# 485.net
KiCad netlist of a schematic drawn in Altium Designer
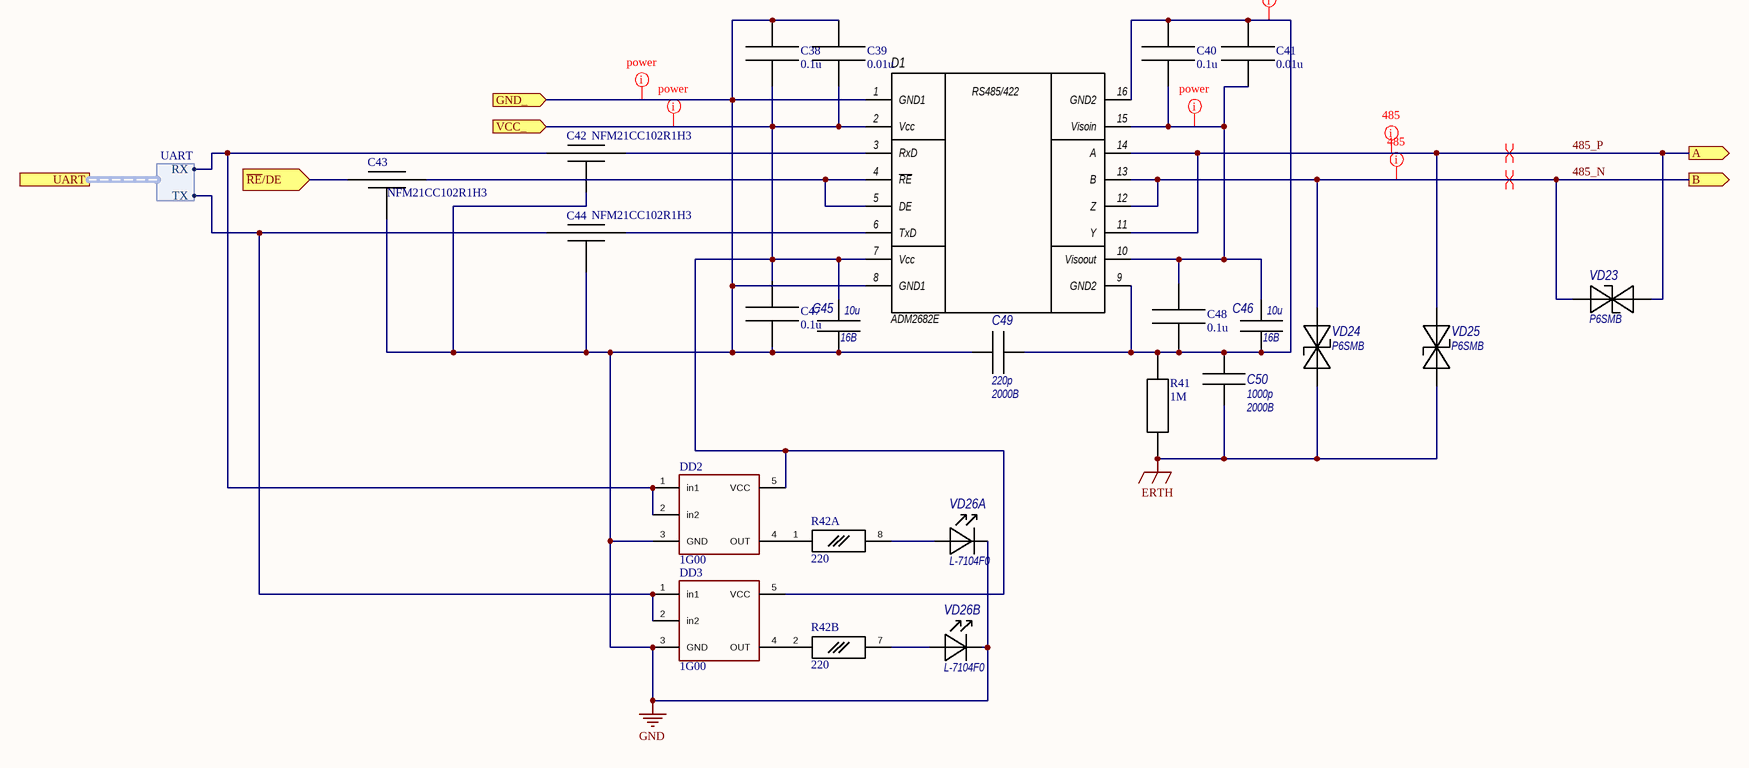
[diagram p0: 485.SchDoc]

(export (version "E")
  (design (tool "Eeschema 10.0.6"))
  (components
    (comp (ref "C38") (value "0.1u") (footprint "cap_0402") (libsource (lib "lib") (part "cap")))
    (comp (ref "C39") (value "0.01u") (footprint "cap_0402") (libsource (lib "lib") (part "cap")))
    (comp (ref "C40") (value "0.1u") (footprint "cap_0402") (libsource (lib "lib") (part "cap")))
    (comp (ref "C41") (value "0.01u") (footprint "cap_0402") (libsource (lib "lib") (part "cap")))
    (comp (ref "C42")
      (value "NFM21CC102R1H3")
      (footprint "NFM21C")
      (libsource (lib "altium-import") (part "root_0_NFM21C_"))
    )
    (comp (ref "C43")
      (value "NFM21CC102R1H3")
      (footprint "NFM21C")
      (libsource (lib "altium-import") (part "root_0_NFM21C_"))
    )
    (comp (ref "C44")
      (value "NFM21CC102R1H3")
      (footprint "NFM21C")
      (libsource (lib "altium-import") (part "root_0_NFM21C_"))
    )
    (comp (ref "C45")
      (value "10u")
      (footprint "C0805_")
      (fields (field (name "VOLTAGE") "16В") (field (name "Comment") "10u 16v"))
      (libsource (lib "altium-import") (part "root_1_Capacitor ceramic_"))
    )
    (comp (ref "C46")
      (value "10u")
      (footprint "C0805_")
      (fields (field (name "VOLTAGE") "16В") (field (name "Comment") "10u 16v"))
      (libsource (lib "altium-import") (part "root_1_Capacitor ceramic_"))
    )
    (comp (ref "C47") (value "0.1u") (footprint "cap_0402") (libsource (lib "lib") (part "cap")))
    (comp (ref "C48") (value "0.1u") (footprint "cap_0402") (libsource (lib "lib") (part "cap")))
    (comp (ref "C49")
      (value "220p")
      (footprint "C1206_")
      (fields (field (name "VOLTAGE") "2000В") (field (name "Comment") "220p 2000v"))
      (libsource (lib "altium-import") (part "root_0_Capacitor ceramic_"))
    )
    (comp (ref "C50")
      (value "1000p")
      (footprint "C1206_")
      (fields (field (name "VOLTAGE") "2000В") (field (name "Comment") "1000p 2000v"))
      (libsource (lib "altium-import") (part "root_1_Capacitor ceramic_"))
    )
    (comp (ref "D1")
      (value "ADM2682E_RS485_422_Isol")
      (footprint "SOIC_16IC_")
      (fields (field (name "TYPE") "ADM2682E"))
      (libsource (lib "altium-import") (part "root_0_ADM2682E_RS485_422_Isol_"))
    )
    (comp (ref "DD2")
      (value "1G00")
      (footprint "sot-23-5")
      (description "2NAND")
      (libsource (lib "lib") (part "1G00"))
    )
    (comp (ref "DD3")
      (value "1G00")
      (footprint "sot-23-5")
      (description "2NAND")
      (libsource (lib "lib") (part "1G00"))
    )
    (comp (ref "R41") (value "1M") (footprint "Lib:0805-res") (libsource (lib "lib") (part "res")))
    (comp (ref "R42")
      (value "220")
      (footprint "YC164")
      (description "YC164")
      (libsource (lib "my_sch_lib") (part "res_array"))
    )
    (comp (ref "VD23")
      (value "PTVS33VS1UTR")
      (footprint "SOD-123")
      (description "PTVS33VS1UTR,115, TVS DIODE 33VWM 53.3VC SOD123W")
      (fields (field (name "TYPE") "P6SMB"))
      (libsource (lib "lib") (part "PTVS33VS1UTR"))
    )
    (comp (ref "VD24")
      (value "PTVS33VS1UTR")
      (footprint "SOD-123")
      (description "PTVS33VS1UTR,115, TVS DIODE 33VWM 53.3VC SOD123W")
      (fields (field (name "TYPE") "P6SMB"))
      (libsource (lib "lib") (part "PTVS33VS1UTR"))
    )
    (comp (ref "VD25")
      (value "PTVS33VS1UTR")
      (footprint "SOD-123")
      (description "PTVS33VS1UTR,115, TVS DIODE 33VWM 53.3VC SOD123W")
      (fields (field (name "TYPE") "P6SMB"))
      (libsource (lib "lib") (part "PTVS33VS1UTR"))
    )
    (comp (ref "VD26")
      (value "Diod_sv_L-7104F0")
      (footprint "L-7104_")
      (fields (field (name "TYPE") "L-7104F0"))
      (libsource (lib "my_sch_lib") (part "Diod_sv_L-7104F0"))
    )
  )
  (nets
    (net (code "2") (name "/485_N") (class "Default")
      (node (ref "D1") (pin "12") (pinfunction "Z_12") (pintype "passive"))
      (node (ref "D1") (pin "13") (pinfunction "B_13") (pintype "passive"))
      (node (ref "VD23") (pin "K") (pinfunction "K_K") (pintype "passive"))
      (node (ref "VD24") (pin "K") (pinfunction "K_K") (pintype "passive"))
    )
    (net (code "3") (name "/485_P") (class "Default")
      (node (ref "D1") (pin "11") (pinfunction "Y_11") (pintype "passive"))
      (node (ref "D1") (pin "14") (pinfunction "A_14") (pintype "passive"))
      (node (ref "VD23") (pin "A") (pinfunction "A_A") (pintype "passive"))
      (node (ref "VD25") (pin "K") (pinfunction "K_K") (pintype "passive"))
    )
    (net (code "4") (name "/VCC_") (class "Default")
      (node (ref "C38") (pin "1") (pinfunction "1_1") (pintype "passive"))
      (node (ref "C39") (pin "2") (pinfunction "2_2") (pintype "passive"))
      (node (ref "C45") (pin "2") (pinfunction "2_2") (pintype "passive"))
      (node (ref "C47") (pin "2") (pinfunction "2_2") (pintype "passive"))
      (node (ref "D1") (pin "2") (pinfunction "Vcc_2") (pintype "passive"))
      (node (ref "D1") (pin "7") (pinfunction "Vcc_7") (pintype "passive"))
      (node (ref "DD2") (pin "5") (pinfunction "VCC_5") (pintype "passive"))
      (node (ref "DD3") (pin "5") (pinfunction "VCC_5") (pintype "passive"))
    )
    (net (code "6") (name "/~{RE}{slash}DE") (class "Default")
      (node (ref "C43") (pin "1") (pinfunction "in_1") (pintype "passive"))
    )
    (net (code "7") (name "ERTH") (class "Default")
      (node (ref "C50") (pin "1") (pinfunction "1_1") (pintype "passive"))
      (node (ref "R41") (pin "1") (pinfunction "1_1") (pintype "passive"))
      (node (ref "VD24") (pin "A") (pinfunction "A_A") (pintype "passive"))
      (node (ref "VD25") (pin "A") (pinfunction "A_A") (pintype "passive"))
    )
    (net (code "8") (name "GND") (class "Default")
      (node (ref "C38") (pin "2") (pinfunction "2_2") (pintype "passive"))
      (node (ref "C39") (pin "1") (pinfunction "1_1") (pintype "passive"))
      (node (ref "C42") (pin "3") (pinfunction "Gnd_3") (pintype "passive"))
      (node (ref "C43") (pin "3") (pinfunction "Gnd_3") (pintype "passive"))
      (node (ref "C44") (pin "3") (pinfunction "Gnd_3") (pintype "passive"))
      (node (ref "C45") (pin "1") (pinfunction "1_1") (pintype "passive"))
      (node (ref "C47") (pin "1") (pinfunction "1_1") (pintype "passive"))
      (node (ref "C49") (pin "1") (pinfunction "1_1") (pintype "passive"))
      (node (ref "D1") (pin "1") (pinfunction "GND1_1") (pintype "passive"))
      (node (ref "D1") (pin "8") (pinfunction "GND1_8") (pintype "passive"))
      (node (ref "DD2") (pin "3") (pinfunction "GND_3") (pintype "passive"))
      (node (ref "DD3") (pin "3") (pinfunction "GND_3") (pintype "passive"))
      (node (ref "VD26") (pin "2") (pinfunction "K1_2") (pintype "passive"))
      (node (ref "VD26") (pin "4") (pinfunction "K2_4") (pintype "passive"))
    )
    (net (code "9") (name "Net-(C40-Pad2)") (class "Default")
      (node (ref "C40") (pin "2") (pinfunction "2_2") (pintype "passive"))
      (node (ref "C41") (pin "1") (pinfunction "1_1") (pintype "passive"))
      (node (ref "C46") (pin "1") (pinfunction "1_1") (pintype "passive"))
      (node (ref "C48") (pin "1") (pinfunction "1_1") (pintype "passive"))
      (node (ref "C49") (pin "2") (pinfunction "2_2") (pintype "passive"))
      (node (ref "C50") (pin "2") (pinfunction "2_2") (pintype "passive"))
      (node (ref "D1") (pin "16") (pinfunction "GND2_16") (pintype "passive"))
      (node (ref "D1") (pin "9") (pinfunction "GND2_9") (pintype "passive"))
      (node (ref "R41") (pin "2") (pinfunction "2_2") (pintype "passive"))
    )
    (net (code "10") (name "Net-(C42-in)") (class "Default")
      (node (ref "C42") (pin "1") (pinfunction "in_1") (pintype "passive"))
      (node (ref "DD2") (pin "1") (pinfunction "in1_1") (pintype "passive"))
      (node (ref "DD2") (pin "2") (pinfunction "in2_2") (pintype "passive"))
    )
    (net (code "11") (name "Net-(C42-out)") (class "Default")
      (node (ref "C42") (pin "2") (pinfunction "out_2") (pintype "passive"))
      (node (ref "D1") (pin "3") (pinfunction "RxD_3") (pintype "passive"))
    )
    (net (code "12") (name "Net-(C43-out)") (class "Default")
      (node (ref "C43") (pin "2") (pinfunction "out_2") (pintype "passive"))
      (node (ref "D1") (pin "4") (pinfunction "~{RE}_4") (pintype "passive"))
      (node (ref "D1") (pin "5") (pinfunction "DE_5") (pintype "passive"))
    )
    (net (code "13") (name "Net-(C44-in)") (class "Default")
      (node (ref "C44") (pin "1") (pinfunction "in_1") (pintype "passive"))
      (node (ref "DD3") (pin "1") (pinfunction "in1_1") (pintype "passive"))
      (node (ref "DD3") (pin "2") (pinfunction "in2_2") (pintype "passive"))
    )
    (net (code "14") (name "Net-(C44-out)") (class "Default")
      (node (ref "C44") (pin "2") (pinfunction "out_2") (pintype "passive"))
      (node (ref "D1") (pin "6") (pinfunction "TxD_6") (pintype "passive"))
    )
    (net (code "15") (name "Net-(D1-Visoin)") (class "Default")
      (node (ref "C40") (pin "1") (pinfunction "1_1") (pintype "passive"))
      (node (ref "C41") (pin "2") (pinfunction "2_2") (pintype "passive"))
      (node (ref "C46") (pin "2") (pinfunction "2_2") (pintype "passive"))
      (node (ref "C48") (pin "2") (pinfunction "2_2") (pintype "passive"))
      (node (ref "D1") (pin "10") (pinfunction "Visoout_10") (pintype "passive"))
      (node (ref "D1") (pin "15") (pinfunction "Visoin_15") (pintype "passive"))
    )
    (net (code "16") (name "Net-(DD2-OUT)") (class "Default")
      (node (ref "DD2") (pin "4") (pinfunction "OUT_4") (pintype "passive"))
      (node (ref "R42") (pin "1") (pinfunction "1_1") (pintype "passive"))
    )
    (net (code "17") (name "Net-(DD3-OUT)") (class "Default")
      (node (ref "DD3") (pin "4") (pinfunction "OUT_4") (pintype "passive"))
      (node (ref "R42") (pin "2") (pinfunction "2_2") (pintype "passive"))
    )
    (net (code "18") (name "Net-(VD26A-A1)") (class "Default")
      (node (ref "R42") (pin "8") (pinfunction "8_8") (pintype "passive"))
      (node (ref "VD26") (pin "1") (pinfunction "A1_1") (pintype "passive"))
    )
    (net (code "19") (name "Net-(VD26B-A2)") (class "Default")
      (node (ref "R42") (pin "7") (pinfunction "7_7") (pintype "passive"))
      (node (ref "VD26") (pin "3") (pinfunction "A2_3") (pintype "passive"))
    )
  )
)
